# sonar_schematic.net
KiCad netlist of a schematic drawn in EasyEDA
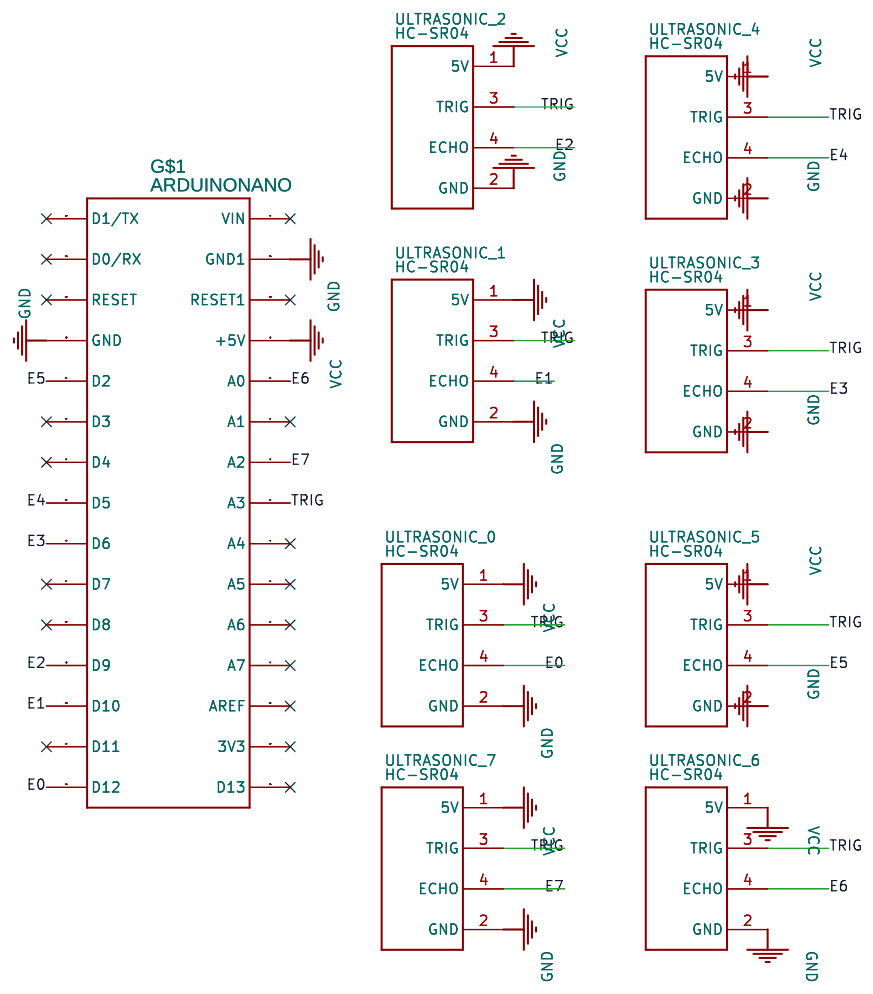
[diagram p0: schematic sheet]

(export (version "E")
  (design (tool "Eeschema 10.0.6"))
  (components
    (comp (ref "G$1")
      (value "ARDUINONANO")
      (fields (field (name "BOM_Manufacturer Part") "?"))
      (libsource (lib "") (part "Unknown_150_-390"))
    )
    (comp (ref "ULTRASONIC_0") (value "HC-SR04") (libsource (lib "") (part "Unknown_305_-180")))
    (comp (ref "ULTRASONIC_1") (value "HC-SR04") (libsource (lib "") (part "Unknown_310_-320")))
    (comp (ref "ULTRASONIC_2") (value "HC-SR04") (libsource (lib "") (part "Unknown_310_-435")))
    (comp (ref "ULTRASONIC_3") (value "HC-SR04") (libsource (lib "") (part "Unknown_435_-315")))
    (comp (ref "ULTRASONIC_4") (value "HC-SR04") (libsource (lib "") (part "Unknown_435_-430")))
    (comp (ref "ULTRASONIC_5") (value "HC-SR04") (libsource (lib "") (part "Unknown_435_-180")))
    (comp (ref "ULTRASONIC_6") (value "HC-SR04") (libsource (lib "") (part "Unknown_435_-70")))
    (comp (ref "ULTRASONIC_7") (value "HC-SR04") (libsource (lib "") (part "Unknown_305_-70")))
  )
  (nets
    (net (code "1") (name "/E0") (class "Default")
      (node (ref "G$1") (pin "D12") (pinfunction "D12_D12") (pintype "bidirectional"))
      (node (ref "ULTRASONIC_0") (pin "4") (pinfunction "ECHO_4") (pintype "bidirectional"))
    )
    (net (code "2") (name "/E1") (class "Default")
      (node (ref "G$1") (pin "D10") (pinfunction "D10_D10") (pintype "bidirectional"))
      (node (ref "ULTRASONIC_1") (pin "4") (pinfunction "ECHO_4") (pintype "bidirectional"))
    )
    (net (code "3") (name "/E2") (class "Default")
      (node (ref "G$1") (pin "D9") (pinfunction "D9_D9") (pintype "bidirectional"))
      (node (ref "ULTRASONIC_2") (pin "4") (pinfunction "ECHO_4") (pintype "bidirectional"))
    )
    (net (code "4") (name "/E3") (class "Default")
      (node (ref "G$1") (pin "D6") (pinfunction "D6_D6") (pintype "bidirectional"))
      (node (ref "ULTRASONIC_3") (pin "4") (pinfunction "ECHO_4") (pintype "bidirectional"))
    )
    (net (code "5") (name "/E4") (class "Default")
      (node (ref "G$1") (pin "D5") (pinfunction "D5_D5") (pintype "bidirectional"))
      (node (ref "ULTRASONIC_4") (pin "4") (pinfunction "ECHO_4") (pintype "bidirectional"))
    )
    (net (code "6") (name "/E5") (class "Default")
      (node (ref "G$1") (pin "D2") (pinfunction "D2_D2") (pintype "bidirectional"))
      (node (ref "ULTRASONIC_5") (pin "4") (pinfunction "ECHO_4") (pintype "bidirectional"))
    )
    (net (code "7") (name "/E6") (class "Default")
      (node (ref "G$1") (pin "A0") (pinfunction "A0_A0") (pintype "bidirectional"))
      (node (ref "ULTRASONIC_6") (pin "4") (pinfunction "ECHO_4") (pintype "bidirectional"))
    )
    (net (code "8") (name "/E7") (class "Default")
      (node (ref "G$1") (pin "A2") (pinfunction "A2_A2") (pintype "bidirectional"))
      (node (ref "ULTRASONIC_7") (pin "4") (pinfunction "ECHO_4") (pintype "bidirectional"))
    )
    (net (code "9") (name "/TRIG") (class "Default")
      (node (ref "G$1") (pin "A3") (pinfunction "A3_A3") (pintype "bidirectional"))
      (node (ref "ULTRASONIC_0") (pin "3") (pinfunction "TRIG_3") (pintype "bidirectional"))
      (node (ref "ULTRASONIC_1") (pin "3") (pinfunction "TRIG_3") (pintype "bidirectional"))
      (node (ref "ULTRASONIC_2") (pin "3") (pinfunction "TRIG_3") (pintype "bidirectional"))
      (node (ref "ULTRASONIC_3") (pin "3") (pinfunction "TRIG_3") (pintype "bidirectional"))
      (node (ref "ULTRASONIC_4") (pin "3") (pinfunction "TRIG_3") (pintype "bidirectional"))
      (node (ref "ULTRASONIC_5") (pin "3") (pinfunction "TRIG_3") (pintype "bidirectional"))
      (node (ref "ULTRASONIC_6") (pin "3") (pinfunction "TRIG_3") (pintype "bidirectional"))
      (node (ref "ULTRASONIC_7") (pin "3") (pinfunction "TRIG_3") (pintype "bidirectional"))
    )
    (net (code "10") (name "GND") (class "Default")
      (node (ref "G$1") (pin "GND") (pinfunction "GND_GND") (pintype "bidirectional"))
      (node (ref "G$1") (pin "GND1") (pinfunction "GND1_GND1") (pintype "bidirectional"))
      (node (ref "ULTRASONIC_0") (pin "2") (pinfunction "GND_2") (pintype "bidirectional"))
      (node (ref "ULTRASONIC_1") (pin "2") (pinfunction "GND_2") (pintype "bidirectional"))
      (node (ref "ULTRASONIC_2") (pin "2") (pinfunction "GND_2") (pintype "bidirectional"))
      (node (ref "ULTRASONIC_3") (pin "2") (pinfunction "GND_2") (pintype "bidirectional"))
      (node (ref "ULTRASONIC_4") (pin "2") (pinfunction "GND_2") (pintype "bidirectional"))
      (node (ref "ULTRASONIC_5") (pin "2") (pinfunction "GND_2") (pintype "bidirectional"))
      (node (ref "ULTRASONIC_6") (pin "2") (pinfunction "GND_2") (pintype "bidirectional"))
      (node (ref "ULTRASONIC_7") (pin "2") (pinfunction "GND_2") (pintype "bidirectional"))
    )
    (net (code "11") (name "VCC") (class "Default")
      (node (ref "G$1") (pin "+5V") (pinfunction "+5V_+5V") (pintype "bidirectional"))
      (node (ref "ULTRASONIC_0") (pin "1") (pinfunction "5V_1") (pintype "bidirectional"))
      (node (ref "ULTRASONIC_1") (pin "1") (pinfunction "5V_1") (pintype "bidirectional"))
      (node (ref "ULTRASONIC_2") (pin "1") (pinfunction "5V_1") (pintype "bidirectional"))
      (node (ref "ULTRASONIC_3") (pin "1") (pinfunction "5V_1") (pintype "bidirectional"))
      (node (ref "ULTRASONIC_4") (pin "1") (pinfunction "5V_1") (pintype "bidirectional"))
      (node (ref "ULTRASONIC_5") (pin "1") (pinfunction "5V_1") (pintype "bidirectional"))
      (node (ref "ULTRASONIC_6") (pin "1") (pinfunction "5V_1") (pintype "bidirectional"))
      (node (ref "ULTRASONIC_7") (pin "1") (pinfunction "5V_1") (pintype "bidirectional"))
    )
    (net (code "12") (name "unconnected-(G$1-Pad3V3)") (class "Default")
      (node (ref "G$1") (pin "3V3") (pinfunction "3V3_3V3") (pintype "bidirectional+no_connect"))
    )
    (net (code "13") (name "unconnected-(G$1-PadA1)") (class "Default")
      (node (ref "G$1") (pin "A1") (pinfunction "A1_A1") (pintype "bidirectional+no_connect"))
    )
    (net (code "14") (name "unconnected-(G$1-PadA4)") (class "Default")
      (node (ref "G$1") (pin "A4") (pinfunction "A4_A4") (pintype "bidirectional+no_connect"))
    )
    (net (code "15") (name "unconnected-(G$1-PadA5)") (class "Default")
      (node (ref "G$1") (pin "A5") (pinfunction "A5_A5") (pintype "bidirectional+no_connect"))
    )
    (net (code "16") (name "unconnected-(G$1-PadA6)") (class "Default")
      (node (ref "G$1") (pin "A6") (pinfunction "A6_A6") (pintype "bidirectional+no_connect"))
    )
    (net (code "17") (name "unconnected-(G$1-PadA7)") (class "Default")
      (node (ref "G$1") (pin "A7") (pinfunction "A7_A7") (pintype "bidirectional+no_connect"))
    )
    (net (code "18") (name "unconnected-(G$1-PadAREF)") (class "Default")
      (node (ref "G$1") (pin "AREF") (pinfunction "AREF_AREF") (pintype "bidirectional+no_connect"))
    )
    (net (code "19") (name "unconnected-(G$1-PadD0{slash}RX)") (class "Default")
      (node (ref "G$1") (pin "D0/RX") (pinfunction "D0/RX_D0/RX") (pintype "bidirectional+no_connect"))
    )
    (net (code "20") (name "unconnected-(G$1-PadD1{slash}TX)") (class "Default")
      (node (ref "G$1") (pin "D1/TX") (pinfunction "D1/TX_D1/TX") (pintype "bidirectional+no_connect"))
    )
    (net (code "21") (name "unconnected-(G$1-PadD3)") (class "Default")
      (node (ref "G$1") (pin "D3") (pinfunction "D3_D3") (pintype "bidirectional+no_connect"))
    )
    (net (code "22") (name "unconnected-(G$1-PadD4)") (class "Default")
      (node (ref "G$1") (pin "D4") (pinfunction "D4_D4") (pintype "bidirectional+no_connect"))
    )
    (net (code "23") (name "unconnected-(G$1-PadD7)") (class "Default")
      (node (ref "G$1") (pin "D7") (pinfunction "D7_D7") (pintype "bidirectional+no_connect"))
    )
    (net (code "24") (name "unconnected-(G$1-PadD8)") (class "Default")
      (node (ref "G$1") (pin "D8") (pinfunction "D8_D8") (pintype "bidirectional+no_connect"))
    )
    (net (code "25") (name "unconnected-(G$1-PadD11)") (class "Default")
      (node (ref "G$1") (pin "D11") (pinfunction "D11_D11") (pintype "bidirectional+no_connect"))
    )
    (net (code "26") (name "unconnected-(G$1-PadD13)") (class "Default")
      (node (ref "G$1") (pin "D13") (pinfunction "D13_D13") (pintype "bidirectional+no_connect"))
    )
    (net (code "27") (name "unconnected-(G$1-PadRESET)") (class "Default")
      (node (ref "G$1") (pin "RESET") (pinfunction "RESET_RESET") (pintype "bidirectional+no_connect"))
    )
    (net (code "28") (name "unconnected-(G$1-PadRESET1)") (class "Default")
      (node (ref "G$1") (pin "RESET1") (pinfunction "RESET1_RESET1") (pintype "bidirectional+no_connect"))
    )
    (net (code "29") (name "unconnected-(G$1-PadVIN)") (class "Default")
      (node (ref "G$1") (pin "VIN") (pinfunction "VIN_VIN") (pintype "bidirectional+no_connect"))
    )
  )
)
